# driver0-3.net
KiCad netlist of a schematic drawn in Altium Designer
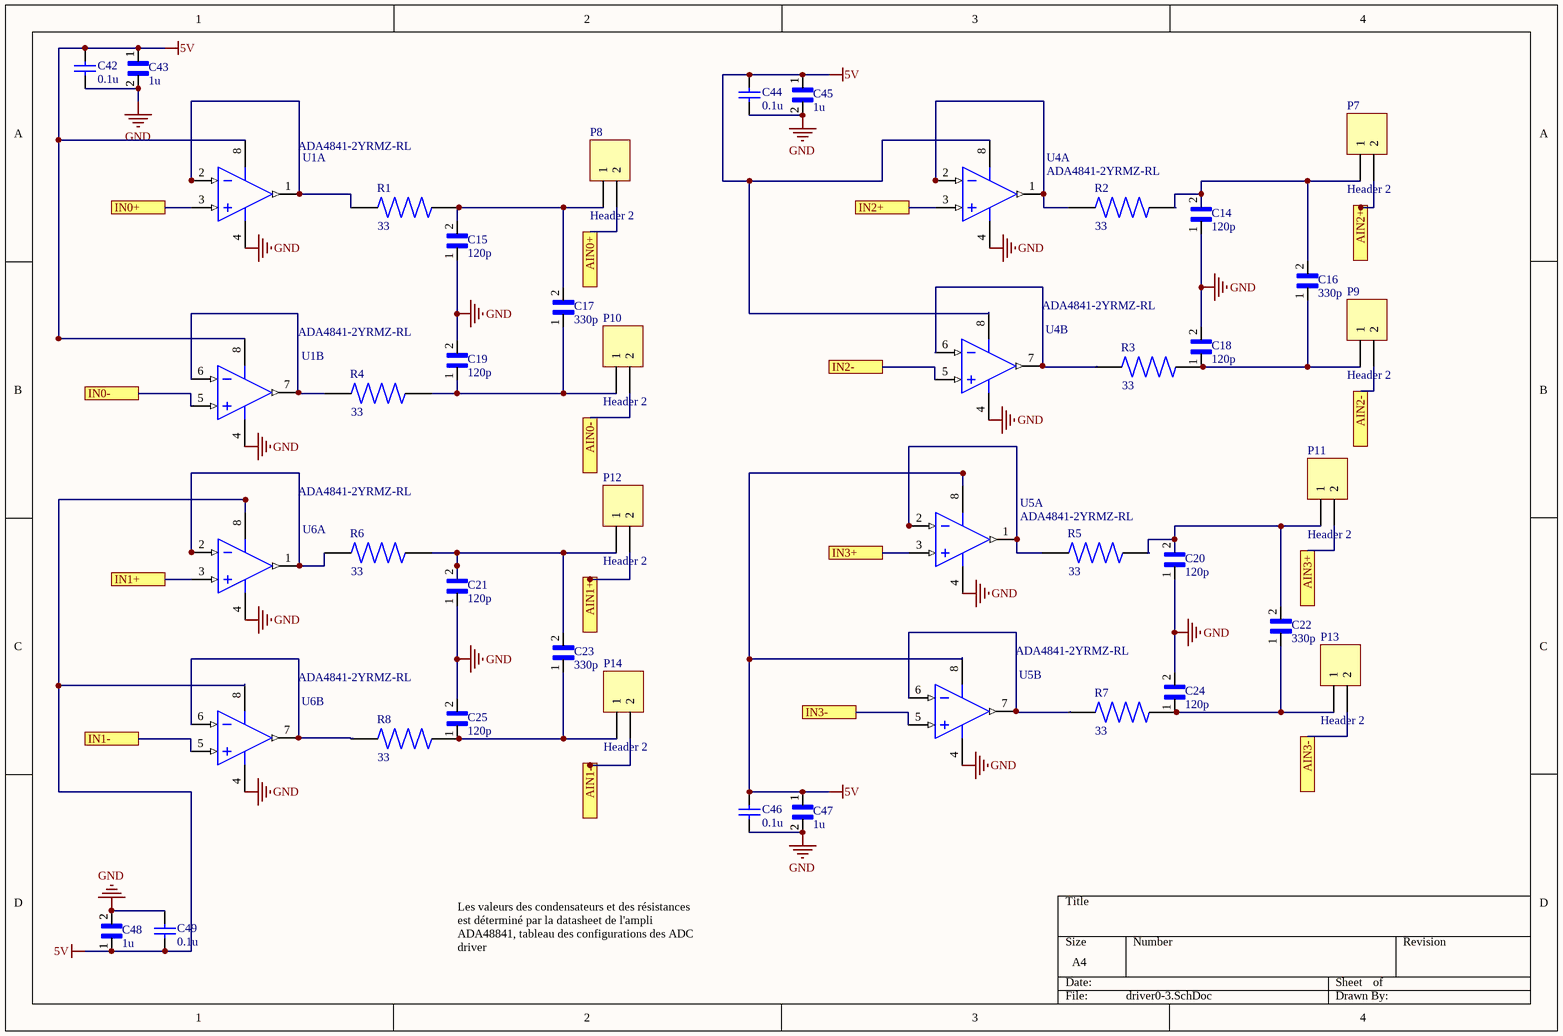
[diagram p0: driver0-3.SchDoc]

(export (version "E")
  (design (tool "Eeschema 10.0.6"))
  (components
    (comp (ref "C14")
      (value "120p")
      (footprint "12061A121JAT2A:CAPC3216X94N")
      (description "CERAMIC CAPACITOR 120PF 100V, C0G, 5%, 1206")
      (fields (field (name "MF") "{'manufacturer': u'AVX'}") (field (name "MP") "12061A121JAT2A"))
      (libsource (lib "12061A121JAT2A") (part "12061A121JAT2A"))
    )
    (comp (ref "C15")
      (value "120p")
      (footprint "12061A121JAT2A:CAPC3216X94N")
      (description "CERAMIC CAPACITOR 120PF 100V, C0G, 5%, 1206")
      (fields (field (name "MF") "{'manufacturer': u'AVX'}") (field (name "MP") "12061A121JAT2A"))
      (libsource (lib "12061A121JAT2A") (part "12061A121JAT2A"))
    )
    (comp (ref "C16")
      (value "330p")
      (footprint "12065A331JAT2A:CAPC3216X94N")
      (fields (field (name "MF") "{'manufacturer': u'AVX'}") (field (name "MP") "12065A331JAT2A"))
      (libsource (lib "12065A331JAT2A") (part "12065A331JAT2A"))
    )
    (comp (ref "C17")
      (value "330p")
      (footprint "12065A331JAT2A:CAPC3216X94N")
      (fields (field (name "MF") "{'manufacturer': u'AVX'}") (field (name "MP") "12065A331JAT2A"))
      (libsource (lib "12065A331JAT2A") (part "12065A331JAT2A"))
    )
    (comp (ref "C18")
      (value "120p")
      (footprint "12061A121JAT2A:CAPC3216X94N")
      (description "CERAMIC CAPACITOR 120PF 100V, C0G, 5%, 1206")
      (fields (field (name "MF") "{'manufacturer': u'AVX'}") (field (name "MP") "12061A121JAT2A"))
      (libsource (lib "12061A121JAT2A") (part "12061A121JAT2A"))
    )
    (comp (ref "C19")
      (value "120p")
      (footprint "12061A121JAT2A:CAPC3216X94N")
      (description "CERAMIC CAPACITOR 120PF 100V, C0G, 5%, 1206")
      (fields (field (name "MF") "{'manufacturer': u'AVX'}") (field (name "MP") "12061A121JAT2A"))
      (libsource (lib "12061A121JAT2A") (part "12061A121JAT2A"))
    )
    (comp (ref "C20")
      (value "120p")
      (footprint "12061A121JAT2A:CAPC3216X94N")
      (description "CERAMIC CAPACITOR 120PF 100V, C0G, 5%, 1206")
      (fields (field (name "MF") "{'manufacturer': u'AVX'}") (field (name "MP") "12061A121JAT2A"))
      (libsource (lib "12061A121JAT2A") (part "12061A121JAT2A"))
    )
    (comp (ref "C21")
      (value "120p")
      (footprint "12061A121JAT2A:CAPC3216X94N")
      (description "CERAMIC CAPACITOR 120PF 100V, C0G, 5%, 1206")
      (fields (field (name "MF") "{'manufacturer': u'AVX'}") (field (name "MP") "12061A121JAT2A"))
      (libsource (lib "12061A121JAT2A") (part "12061A121JAT2A"))
    )
    (comp (ref "C22")
      (value "330p")
      (footprint "12065A331JAT2A:CAPC3216X94N")
      (fields (field (name "MF") "{'manufacturer': u'AVX'}") (field (name "MP") "12065A331JAT2A"))
      (libsource (lib "12065A331JAT2A") (part "12065A331JAT2A"))
    )
    (comp (ref "C23")
      (value "330p")
      (footprint "12065A331JAT2A:CAPC3216X94N")
      (fields (field (name "MF") "{'manufacturer': u'AVX'}") (field (name "MP") "12065A331JAT2A"))
      (libsource (lib "12065A331JAT2A") (part "12065A331JAT2A"))
    )
    (comp (ref "C24")
      (value "120p")
      (footprint "12061A121JAT2A:CAPC3216X94N")
      (description "CERAMIC CAPACITOR 120PF 100V, C0G, 5%, 1206")
      (fields (field (name "MF") "{'manufacturer': u'AVX'}") (field (name "MP") "12061A121JAT2A"))
      (libsource (lib "12061A121JAT2A") (part "12061A121JAT2A"))
    )
    (comp (ref "C25")
      (value "120p")
      (footprint "12061A121JAT2A:CAPC3216X94N")
      (description "CERAMIC CAPACITOR 120PF 100V, C0G, 5%, 1206")
      (fields (field (name "MF") "{'manufacturer': u'AVX'}") (field (name "MP") "12061A121JAT2A"))
      (libsource (lib "12061A121JAT2A") (part "12061A121JAT2A"))
    )
    (comp (ref "C42")
      (value "0.1u")
      (footprint "CAPC3216X94X50ML20T25")
      (description "Chip Capacitor, Ceramic, 100 nF, 10%, 50 V, 1206, RoHS, Tape and Reel")
      (fields (field (name "MANUFACTURER") "AVX"))
      (libsource (lib "Altium Content Vault") (part "CAP-NP-2"))
    )
    (comp (ref "C43")
      (value "1u")
      (footprint "1206YC105KAT2A:CAPC3216X127N")
      (description "Cap Ceramic 1uF 16V X7R 10% SMD 1206 125ÂÂŽ T/R")
      (fields (field (name "MF") "{'manufacturer': u'AVX'}") (field (name "MP") "1206YC105KAT2A"))
      (libsource (lib "1206YC105KAT2A") (part "1206YC105KAT2A"))
    )
    (comp (ref "C44")
      (value "0.1u")
      (footprint "CAPC3216X94X50ML20T25")
      (description "Chip Capacitor, Ceramic, 100 nF, 10%, 50 V, 1206, RoHS, Tape and Reel")
      (fields (field (name "MANUFACTURER") "AVX"))
      (libsource (lib "Altium Content Vault") (part "CAP-NP-2"))
    )
    (comp (ref "C45")
      (value "1u")
      (footprint "1206YC105KAT2A:CAPC3216X127N")
      (description "Cap Ceramic 1uF 16V X7R 10% SMD 1206 125ÂÂŽ T/R")
      (fields (field (name "MF") "{'manufacturer': u'AVX'}") (field (name "MP") "1206YC105KAT2A"))
      (libsource (lib "1206YC105KAT2A") (part "1206YC105KAT2A"))
    )
    (comp (ref "C46")
      (value "0.1u")
      (footprint "CAPC3216X94X50ML20T25")
      (description "Chip Capacitor, Ceramic, 100 nF, 10%, 50 V, 1206, RoHS, Tape and Reel")
      (fields (field (name "MANUFACTURER") "AVX"))
      (libsource (lib "Altium Content Vault") (part "CAP-NP-2"))
    )
    (comp (ref "C47")
      (value "1u")
      (footprint "1206YC105KAT2A:CAPC3216X127N")
      (description "Cap Ceramic 1uF 16V X7R 10% SMD 1206 125ÂÂŽ T/R")
      (fields (field (name "MF") "{'manufacturer': u'AVX'}") (field (name "MP") "1206YC105KAT2A"))
      (libsource (lib "1206YC105KAT2A") (part "1206YC105KAT2A"))
    )
    (comp (ref "C48")
      (value "1u")
      (footprint "1206YC105KAT2A:CAPC3216X127N")
      (description "Cap Ceramic 1uF 16V X7R 10% SMD 1206 125ÂÂŽ T/R")
      (fields (field (name "MF") "{'manufacturer': u'AVX'}") (field (name "MP") "1206YC105KAT2A"))
      (libsource (lib "") (part "1206YC105KAT2A_1"))
    )
    (comp (ref "C49")
      (value "0.1u")
      (footprint "CAPC3216X94X50ML20T25")
      (description "Chip Capacitor, Ceramic, 100 nF, 10%, 50 V, 1206, RoHS, Tape and Reel")
      (fields (field (name "MANUFACTURER") "AVX"))
      (libsource (lib "Altium Content Vault") (part "CAP-NP-2"))
    )
    (comp (ref "P7")
      (value "Header 2")
      (footprint "HDR1X2")
      (description "Header, 2-Pin")
      (fields (field (name "PUBLISHER") "Altium Limited"))
      (libsource (lib "Miscellaneous Connectors") (part "Header 2"))
    )
    (comp (ref "P8")
      (value "Header 2")
      (footprint "HDR1X2")
      (description "Header, 2-Pin")
      (fields (field (name "PUBLISHER") "Altium Limited"))
      (libsource (lib "Miscellaneous Connectors") (part "Header 2"))
    )
    (comp (ref "P9")
      (value "Header 2")
      (footprint "HDR1X2")
      (description "Header, 2-Pin")
      (fields (field (name "PUBLISHER") "Altium Limited"))
      (libsource (lib "Miscellaneous Connectors") (part "Header 2"))
    )
    (comp (ref "P10")
      (value "Header 2")
      (footprint "HDR1X2")
      (description "Header, 2-Pin")
      (fields (field (name "PUBLISHER") "Altium Limited"))
      (libsource (lib "Miscellaneous Connectors") (part "Header 2"))
    )
    (comp (ref "P11")
      (value "Header 2")
      (footprint "HDR1X2")
      (description "Header, 2-Pin")
      (fields (field (name "PUBLISHER") "Altium Limited"))
      (libsource (lib "Miscellaneous Connectors") (part "Header 2"))
    )
    (comp (ref "P12")
      (value "Header 2")
      (footprint "HDR1X2")
      (description "Header, 2-Pin")
      (fields (field (name "PUBLISHER") "Altium Limited"))
      (libsource (lib "Miscellaneous Connectors") (part "Header 2"))
    )
    (comp (ref "P13")
      (value "Header 2")
      (footprint "HDR1X2")
      (description "Header, 2-Pin")
      (fields (field (name "PUBLISHER") "Altium Limited"))
      (libsource (lib "Miscellaneous Connectors") (part "Header 2"))
    )
    (comp (ref "P14")
      (value "Header 2")
      (footprint "HDR1X2")
      (description "Header, 2-Pin")
      (fields (field (name "PUBLISHER") "Altium Limited"))
      (libsource (lib "Miscellaneous Connectors") (part "Header 2"))
    )
    (comp (ref "R1")
      (value "33")
      (footprint "RTAN1206BKE33R0:RESC3116X75N")
      (fields
        (field (name "MF") "{'manufacturer': u'Stackpole Electronics Inc'}")
        (field (name "MP") "RTAN1206BKE33R0")
      )
      (libsource (lib "RTAN1206BKE33R0") (part "RTAN1206BKE33R0"))
    )
    (comp (ref "R2")
      (value "33")
      (footprint "RTAN1206BKE33R0:RESC3116X75N")
      (fields
        (field (name "MF") "{'manufacturer': u'Stackpole Electronics Inc'}")
        (field (name "MP") "RTAN1206BKE33R0")
      )
      (libsource (lib "RTAN1206BKE33R0") (part "RTAN1206BKE33R0"))
    )
    (comp (ref "R3")
      (value "33")
      (footprint "RTAN1206BKE33R0:RESC3116X75N")
      (fields
        (field (name "MF") "{'manufacturer': u'Stackpole Electronics Inc'}")
        (field (name "MP") "RTAN1206BKE33R0")
      )
      (libsource (lib "RTAN1206BKE33R0") (part "RTAN1206BKE33R0"))
    )
    (comp (ref "R4")
      (value "33")
      (footprint "RTAN1206BKE33R0:RESC3116X75N")
      (fields
        (field (name "MF") "{'manufacturer': u'Stackpole Electronics Inc'}")
        (field (name "MP") "RTAN1206BKE33R0")
      )
      (libsource (lib "RTAN1206BKE33R0") (part "RTAN1206BKE33R0"))
    )
    (comp (ref "R5")
      (value "33")
      (footprint "RTAN1206BKE33R0:RESC3116X75N")
      (fields
        (field (name "MF") "{'manufacturer': u'Stackpole Electronics Inc'}")
        (field (name "MP") "RTAN1206BKE33R0")
      )
      (libsource (lib "RTAN1206BKE33R0") (part "RTAN1206BKE33R0"))
    )
    (comp (ref "R6")
      (value "33")
      (footprint "RTAN1206BKE33R0:RESC3116X75N")
      (fields
        (field (name "MF") "{'manufacturer': u'Stackpole Electronics Inc'}")
        (field (name "MP") "RTAN1206BKE33R0")
      )
      (libsource (lib "RTAN1206BKE33R0") (part "RTAN1206BKE33R0"))
    )
    (comp (ref "R7")
      (value "33")
      (footprint "RTAN1206BKE33R0:RESC3116X75N")
      (fields
        (field (name "MF") "{'manufacturer': u'Stackpole Electronics Inc'}")
        (field (name "MP") "RTAN1206BKE33R0")
      )
      (libsource (lib "RTAN1206BKE33R0") (part "RTAN1206BKE33R0"))
    )
    (comp (ref "R8")
      (value "33")
      (footprint "RTAN1206BKE33R0:RESC3116X75N")
      (fields
        (field (name "MF") "{'manufacturer': u'Stackpole Electronics Inc'}")
        (field (name "MP") "RTAN1206BKE33R0")
      )
      (libsource (lib "RTAN1206BKE33R0") (part "RTAN1206BKE33R0"))
    )
    (comp (ref "U1")
      (value "ADA4841-2YRMZ-RL")
      (footprint "ADI-RM-8_M")
      (fields (field (name "MANUFACTURER") "Analog Devices") (field (name "GENERIC PART NUMBER") "ADA4841-2"))
      (libsource (lib "Altium Content Vault") (part "ADI-AD8XXX_823_A48X1-X-8"))
    )
    (comp (ref "U4")
      (value "ADA4841-2YRMZ-RL")
      (footprint "ADI-RM-8_M")
      (fields (field (name "MANUFACTURER") "Analog Devices") (field (name "GENERIC PART NUMBER") "ADA4841-2"))
      (libsource (lib "Altium Content Vault") (part "ADI-AD8XXX_823_A48X1-X-8"))
    )
    (comp (ref "U5")
      (value "ADA4841-2YRMZ-RL")
      (footprint "ADI-RM-8_M")
      (fields (field (name "MANUFACTURER") "Analog Devices") (field (name "GENERIC PART NUMBER") "ADA4841-2"))
      (libsource (lib "Altium Content Vault") (part "ADI-AD8XXX_823_A48X1-X-8"))
    )
    (comp (ref "U6")
      (value "ADA4841-2YRMZ-RL")
      (footprint "ADI-RM-8_M")
      (fields (field (name "MANUFACTURER") "Analog Devices") (field (name "GENERIC PART NUMBER") "ADA4841-2"))
      (libsource (lib "Altium Content Vault") (part "ADI-AD8XXX_823_A48X1-X-8"))
    )
  )
  (nets
    (net (code "1") (name "/AIN0+") (class "Default")
      (node (ref "P8") (pin "2") (pinfunction "2_2") (pintype "passive"))
    )
    (net (code "2") (name "/AIN0-") (class "Default")
      (node (ref "P10") (pin "2") (pinfunction "2_2") (pintype "passive"))
    )
    (net (code "3") (name "/AIN1+") (class "Default")
      (node (ref "P12") (pin "2") (pinfunction "2_2") (pintype "passive"))
    )
    (net (code "4") (name "/AIN1-") (class "Default")
      (node (ref "P14") (pin "2") (pinfunction "2_2") (pintype "passive"))
    )
    (net (code "5") (name "/AIN2+") (class "Default")
      (node (ref "P7") (pin "2") (pinfunction "2_2") (pintype "passive"))
    )
    (net (code "6") (name "/AIN2-") (class "Default")
      (node (ref "P9") (pin "2") (pinfunction "2_2") (pintype "passive"))
    )
    (net (code "7") (name "/AIN3+") (class "Default")
      (node (ref "P11") (pin "2") (pinfunction "2_2") (pintype "passive"))
    )
    (net (code "8") (name "/AIN3-") (class "Default")
      (node (ref "P13") (pin "2") (pinfunction "2_2") (pintype "passive"))
    )
    (net (code "9") (name "/IN0+") (class "Default")
      (node (ref "U1") (pin "3") (pinfunction "+IN_1_3") (pintype "input"))
    )
    (net (code "10") (name "/IN0-") (class "Default")
      (node (ref "U1") (pin "5") (pinfunction "+IN_2_5") (pintype "input"))
    )
    (net (code "11") (name "/IN1+") (class "Default")
      (node (ref "U6") (pin "3") (pinfunction "+IN_1_3") (pintype "input"))
    )
    (net (code "12") (name "/IN1-") (class "Default")
      (node (ref "U6") (pin "5") (pinfunction "+IN_2_5") (pintype "input"))
    )
    (net (code "13") (name "/IN2+") (class "Default")
      (node (ref "U4") (pin "3") (pinfunction "+IN_1_3") (pintype "input"))
    )
    (net (code "14") (name "/IN2-") (class "Default")
      (node (ref "U4") (pin "5") (pinfunction "+IN_2_5") (pintype "input"))
    )
    (net (code "15") (name "/IN3+") (class "Default")
      (node (ref "U5") (pin "3") (pinfunction "+IN_1_3") (pintype "input"))
    )
    (net (code "16") (name "/IN3-") (class "Default")
      (node (ref "U5") (pin "5") (pinfunction "+IN_2_5") (pintype "input"))
    )
    (net (code "17") (name "5V") (class "Default")
      (node (ref "C42") (pin "1") (pinfunction "1_1") (pintype "passive"))
      (node (ref "C43") (pin "1") (pinfunction "1_1") (pintype "passive"))
      (node (ref "C44") (pin "1") (pinfunction "1_1") (pintype "passive"))
      (node (ref "C45") (pin "1") (pinfunction "1_1") (pintype "passive"))
      (node (ref "C46") (pin "1") (pinfunction "1_1") (pintype "passive"))
      (node (ref "C47") (pin "1") (pinfunction "1_1") (pintype "passive"))
      (node (ref "C48") (pin "1") (pinfunction "1_1") (pintype "passive"))
      (node (ref "C49") (pin "1") (pinfunction "1_1") (pintype "passive"))
      (node (ref "U1") (pin "8") (pinfunction "+VS_8") (pintype "power_in"))
      (node (ref "U4") (pin "8") (pinfunction "+VS_8") (pintype "power_in"))
      (node (ref "U5") (pin "8") (pinfunction "+VS_8") (pintype "power_in"))
      (node (ref "U6") (pin "8") (pinfunction "+VS_8") (pintype "power_in"))
    )
    (net (code "18") (name "GND") (class "Default")
      (node (ref "C14") (pin "1") (pinfunction "1_1") (pintype "passive"))
      (node (ref "C15") (pin "1") (pinfunction "1_1") (pintype "passive"))
      (node (ref "C18") (pin "2") (pinfunction "2_2") (pintype "passive"))
      (node (ref "C19") (pin "2") (pinfunction "2_2") (pintype "passive"))
      (node (ref "C20") (pin "1") (pinfunction "1_1") (pintype "passive"))
      (node (ref "C21") (pin "1") (pinfunction "1_1") (pintype "passive"))
      (node (ref "C24") (pin "2") (pinfunction "2_2") (pintype "passive"))
      (node (ref "C25") (pin "2") (pinfunction "2_2") (pintype "passive"))
      (node (ref "C42") (pin "2") (pinfunction "2_2") (pintype "passive"))
      (node (ref "C43") (pin "2") (pinfunction "2_2") (pintype "passive"))
      (node (ref "C44") (pin "2") (pinfunction "2_2") (pintype "passive"))
      (node (ref "C45") (pin "2") (pinfunction "2_2") (pintype "passive"))
      (node (ref "C46") (pin "2") (pinfunction "2_2") (pintype "passive"))
      (node (ref "C47") (pin "2") (pinfunction "2_2") (pintype "passive"))
      (node (ref "C48") (pin "2") (pinfunction "2_2") (pintype "passive"))
      (node (ref "C49") (pin "2") (pinfunction "2_2") (pintype "passive"))
      (node (ref "U1") (pin "4") (pinfunction "-VS_4") (pintype "power_in"))
      (node (ref "U4") (pin "4") (pinfunction "-VS_4") (pintype "power_in"))
      (node (ref "U5") (pin "4") (pinfunction "-VS_4") (pintype "power_in"))
      (node (ref "U6") (pin "4") (pinfunction "-VS_4") (pintype "power_in"))
    )
    (net (code "19") (name "Net-(C14-Pad2)") (class "Default")
      (node (ref "C14") (pin "2") (pinfunction "2_2") (pintype "passive"))
      (node (ref "C16") (pin "2") (pinfunction "2_2") (pintype "passive"))
      (node (ref "P7") (pin "1") (pinfunction "1_1") (pintype "passive"))
      (node (ref "R2") (pin "2") (pinfunction "2_2") (pintype "passive"))
    )
    (net (code "20") (name "Net-(C15-Pad2)") (class "Default")
      (node (ref "C15") (pin "2") (pinfunction "2_2") (pintype "passive"))
      (node (ref "C17") (pin "2") (pinfunction "2_2") (pintype "passive"))
      (node (ref "P8") (pin "1") (pinfunction "1_1") (pintype "passive"))
      (node (ref "R1") (pin "2") (pinfunction "2_2") (pintype "passive"))
    )
    (net (code "21") (name "Net-(C16-Pad1)") (class "Default")
      (node (ref "C16") (pin "1") (pinfunction "1_1") (pintype "passive"))
      (node (ref "C18") (pin "1") (pinfunction "1_1") (pintype "passive"))
      (node (ref "P9") (pin "1") (pinfunction "1_1") (pintype "passive"))
      (node (ref "R3") (pin "2") (pinfunction "2_2") (pintype "passive"))
    )
    (net (code "22") (name "Net-(C17-Pad1)") (class "Default")
      (node (ref "C17") (pin "1") (pinfunction "1_1") (pintype "passive"))
      (node (ref "C19") (pin "1") (pinfunction "1_1") (pintype "passive"))
      (node (ref "P10") (pin "1") (pinfunction "1_1") (pintype "passive"))
      (node (ref "R4") (pin "2") (pinfunction "2_2") (pintype "passive"))
    )
    (net (code "23") (name "Net-(C20-Pad2)") (class "Default")
      (node (ref "C20") (pin "2") (pinfunction "2_2") (pintype "passive"))
      (node (ref "C22") (pin "2") (pinfunction "2_2") (pintype "passive"))
      (node (ref "P11") (pin "1") (pinfunction "1_1") (pintype "passive"))
      (node (ref "R5") (pin "2") (pinfunction "2_2") (pintype "passive"))
    )
    (net (code "24") (name "Net-(C21-Pad2)") (class "Default")
      (node (ref "C21") (pin "2") (pinfunction "2_2") (pintype "passive"))
      (node (ref "C23") (pin "2") (pinfunction "2_2") (pintype "passive"))
      (node (ref "P12") (pin "1") (pinfunction "1_1") (pintype "passive"))
      (node (ref "R6") (pin "2") (pinfunction "2_2") (pintype "passive"))
    )
    (net (code "25") (name "Net-(C22-Pad1)") (class "Default")
      (node (ref "C22") (pin "1") (pinfunction "1_1") (pintype "passive"))
      (node (ref "C24") (pin "1") (pinfunction "1_1") (pintype "passive"))
      (node (ref "P13") (pin "1") (pinfunction "1_1") (pintype "passive"))
      (node (ref "R7") (pin "2") (pinfunction "2_2") (pintype "passive"))
    )
    (net (code "26") (name "Net-(C23-Pad1)") (class "Default")
      (node (ref "C23") (pin "1") (pinfunction "1_1") (pintype "passive"))
      (node (ref "C25") (pin "1") (pinfunction "1_1") (pintype "passive"))
      (node (ref "P14") (pin "1") (pinfunction "1_1") (pintype "passive"))
      (node (ref "R8") (pin "2") (pinfunction "2_2") (pintype "passive"))
    )
    (net (code "27") (name "Net-(U1A--IN_1)") (class "Default")
      (node (ref "R1") (pin "1") (pinfunction "1_1") (pintype "passive"))
      (node (ref "U1") (pin "1") (pinfunction "OUT_1_1") (pintype "output"))
      (node (ref "U1") (pin "2") (pinfunction "-IN_1_2") (pintype "input"))
    )
    (net (code "28") (name "Net-(U1B--IN_2)") (class "Default")
      (node (ref "R4") (pin "1") (pinfunction "1_1") (pintype "passive"))
      (node (ref "U1") (pin "6") (pinfunction "-IN_2_6") (pintype "input"))
      (node (ref "U1") (pin "7") (pinfunction "OUT_2_7") (pintype "output"))
    )
    (net (code "29") (name "Net-(U4A--IN_1)") (class "Default")
      (node (ref "R2") (pin "1") (pinfunction "1_1") (pintype "passive"))
      (node (ref "U4") (pin "1") (pinfunction "OUT_1_1") (pintype "output"))
      (node (ref "U4") (pin "2") (pinfunction "-IN_1_2") (pintype "input"))
    )
    (net (code "30") (name "Net-(U4B--IN_2)") (class "Default")
      (node (ref "R3") (pin "1") (pinfunction "1_1") (pintype "passive"))
      (node (ref "U4") (pin "6") (pinfunction "-IN_2_6") (pintype "input"))
      (node (ref "U4") (pin "7") (pinfunction "OUT_2_7") (pintype "output"))
    )
    (net (code "31") (name "Net-(U5A--IN_1)") (class "Default")
      (node (ref "R5") (pin "1") (pinfunction "1_1") (pintype "passive"))
      (node (ref "U5") (pin "1") (pinfunction "OUT_1_1") (pintype "output"))
      (node (ref "U5") (pin "2") (pinfunction "-IN_1_2") (pintype "input"))
    )
    (net (code "32") (name "Net-(U5B--IN_2)") (class "Default")
      (node (ref "R7") (pin "1") (pinfunction "1_1") (pintype "passive"))
      (node (ref "U5") (pin "6") (pinfunction "-IN_2_6") (pintype "input"))
      (node (ref "U5") (pin "7") (pinfunction "OUT_2_7") (pintype "output"))
    )
    (net (code "33") (name "Net-(U6A--IN_1)") (class "Default")
      (node (ref "R6") (pin "1") (pinfunction "1_1") (pintype "passive"))
      (node (ref "U6") (pin "1") (pinfunction "OUT_1_1") (pintype "output"))
      (node (ref "U6") (pin "2") (pinfunction "-IN_1_2") (pintype "input"))
    )
    (net (code "34") (name "Net-(U6B--IN_2)") (class "Default")
      (node (ref "R8") (pin "1") (pinfunction "1_1") (pintype "passive"))
      (node (ref "U6") (pin "6") (pinfunction "-IN_2_6") (pintype "input"))
      (node (ref "U6") (pin "7") (pinfunction "OUT_2_7") (pintype "output"))
    )
  )
)
